# Monitait_V2.net
KiCad netlist of a schematic drawn in Altium Designer
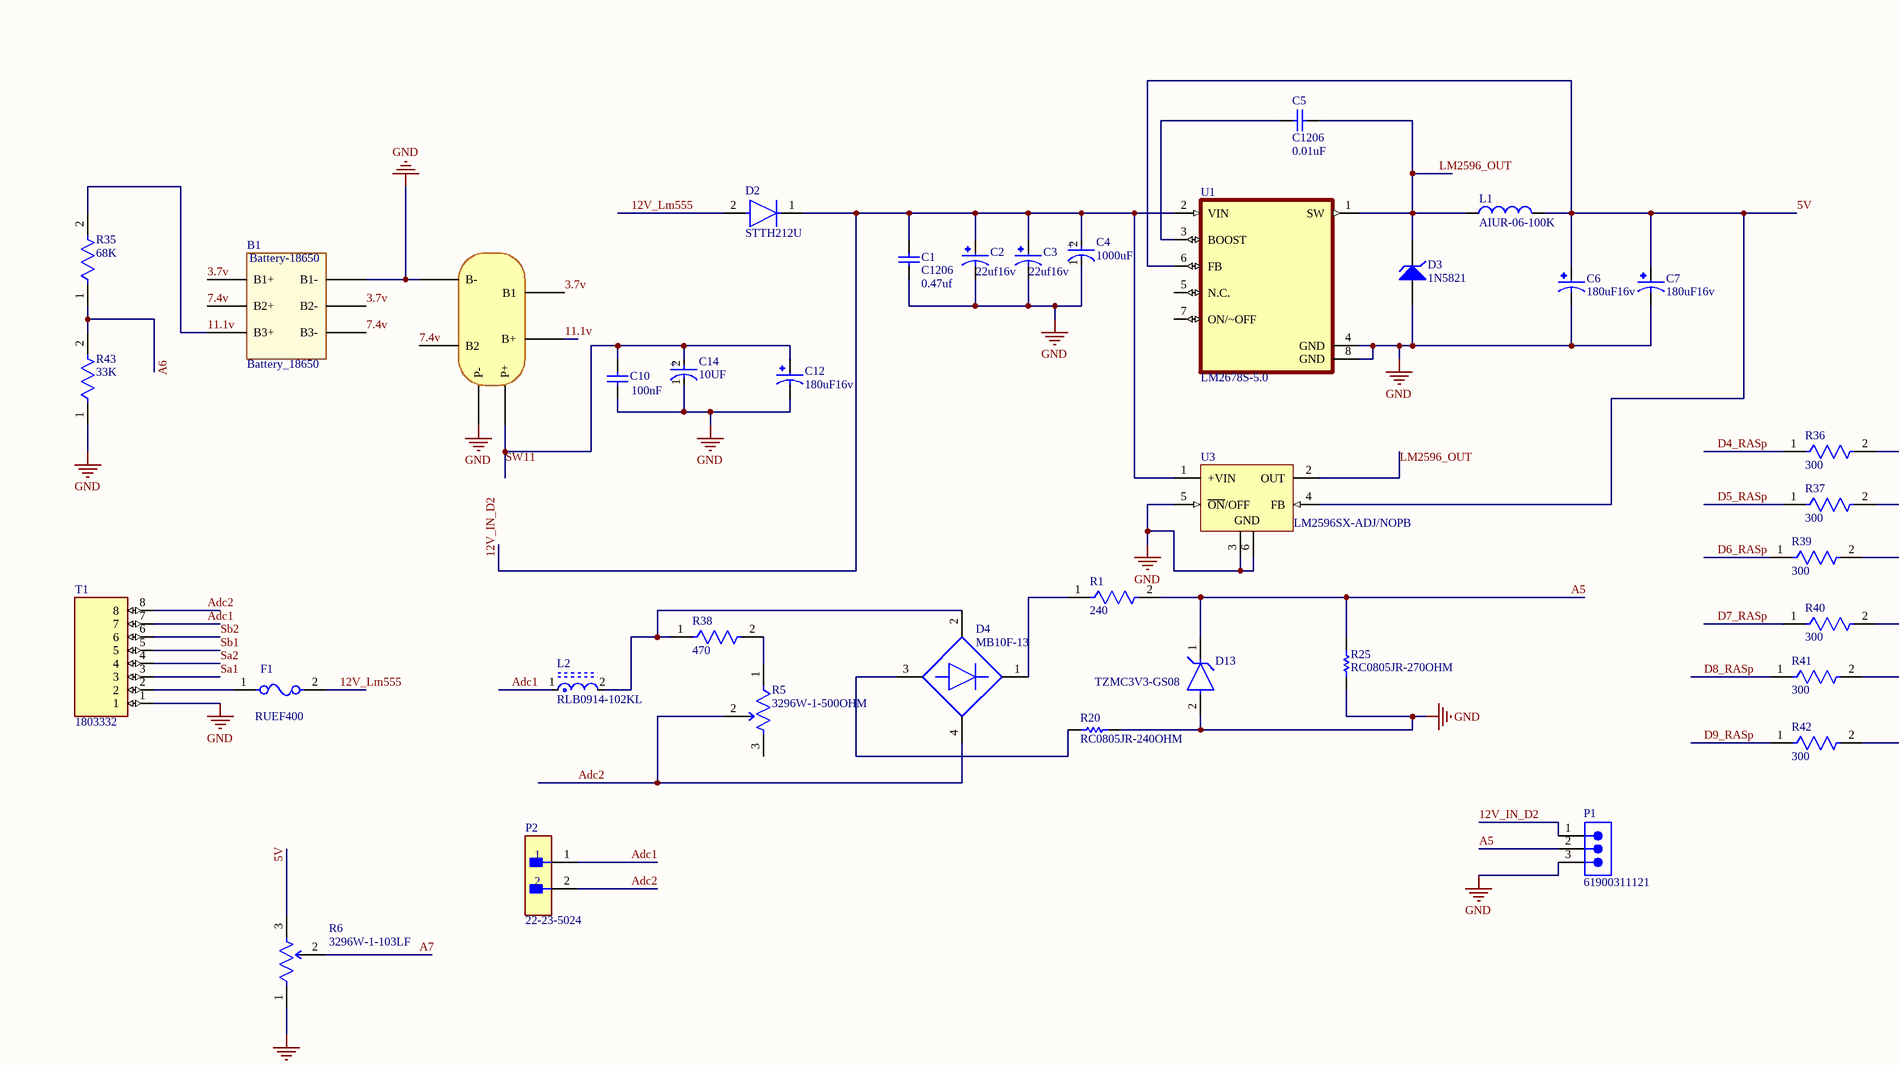
[diagram p0: Monitait_V2.SchDoc, top left]
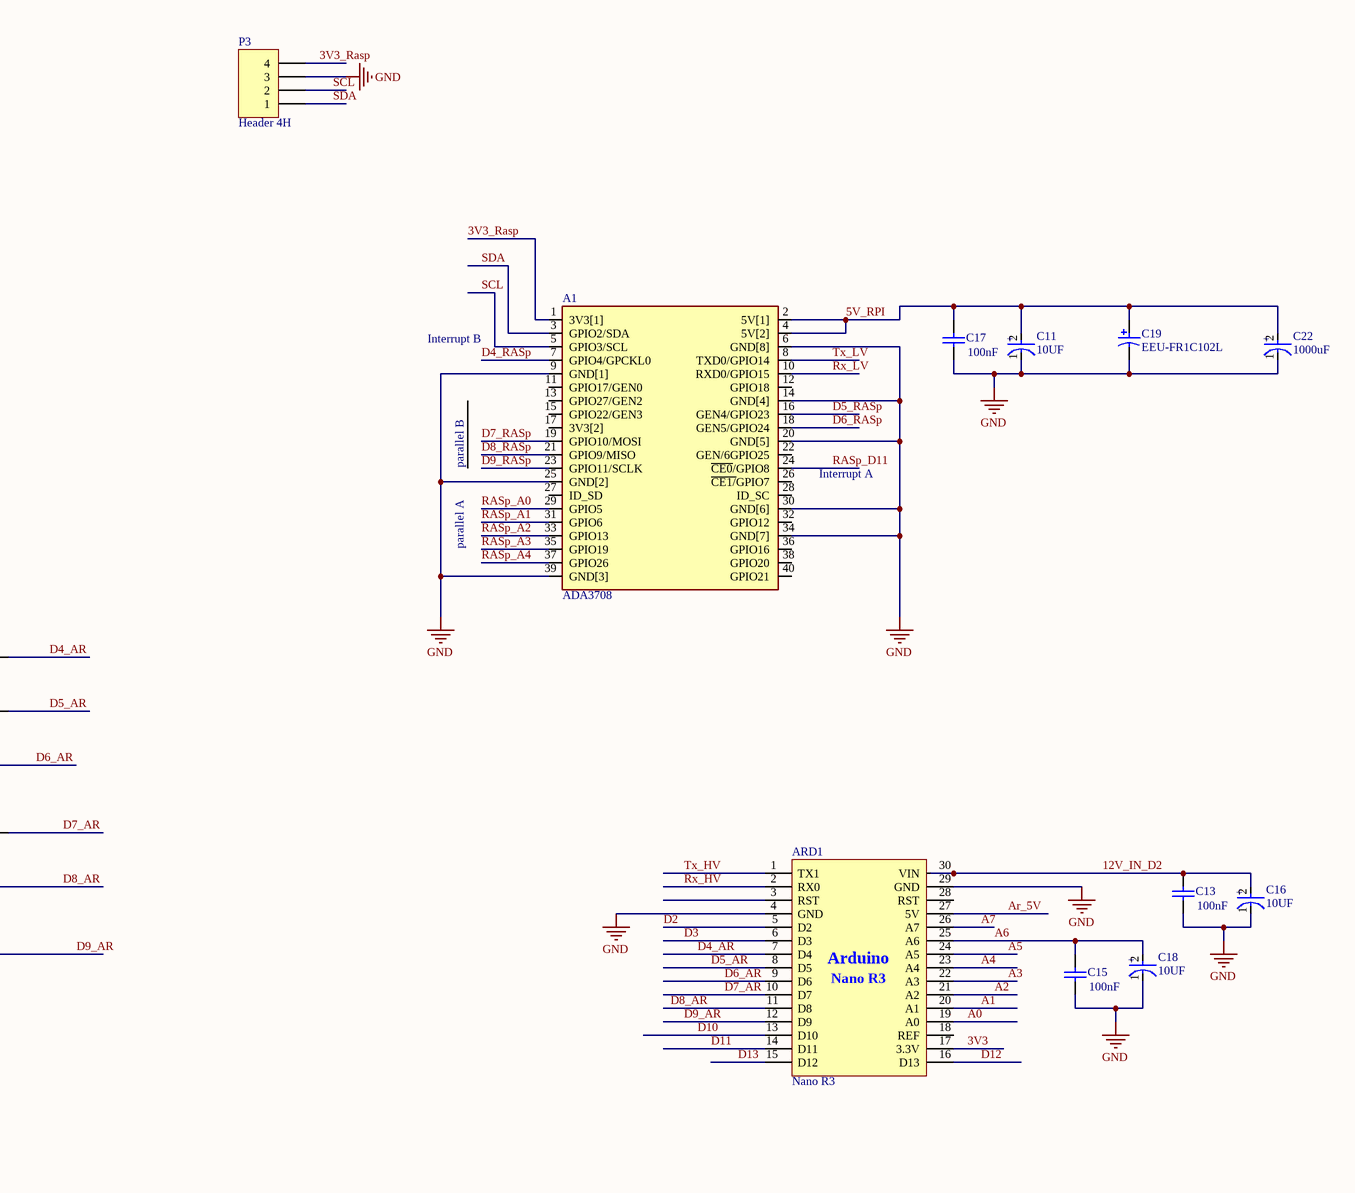
[diagram p1: Monitait_V2.SchDoc, top middle]
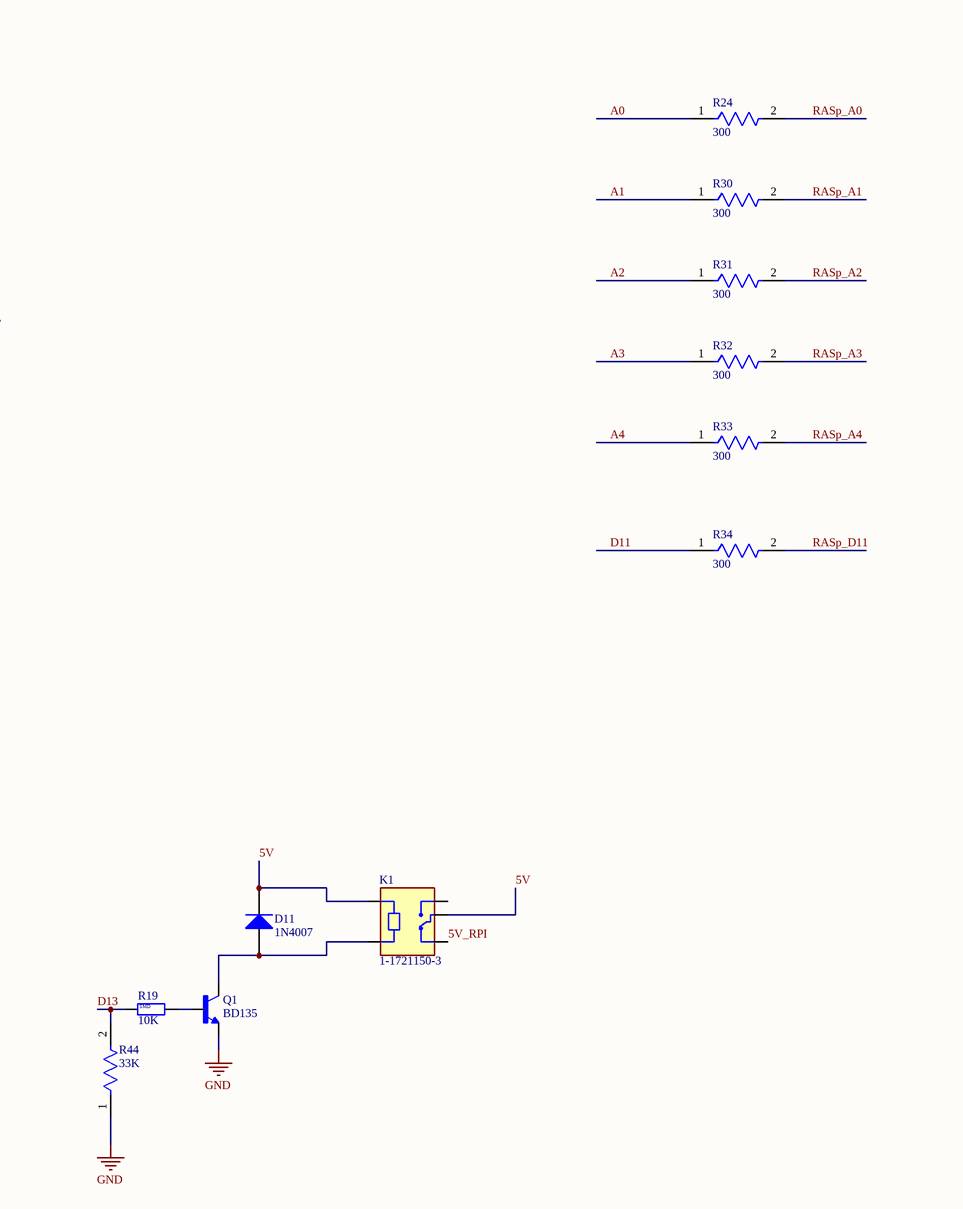
[diagram p2: Monitait_V2.SchDoc, top right]
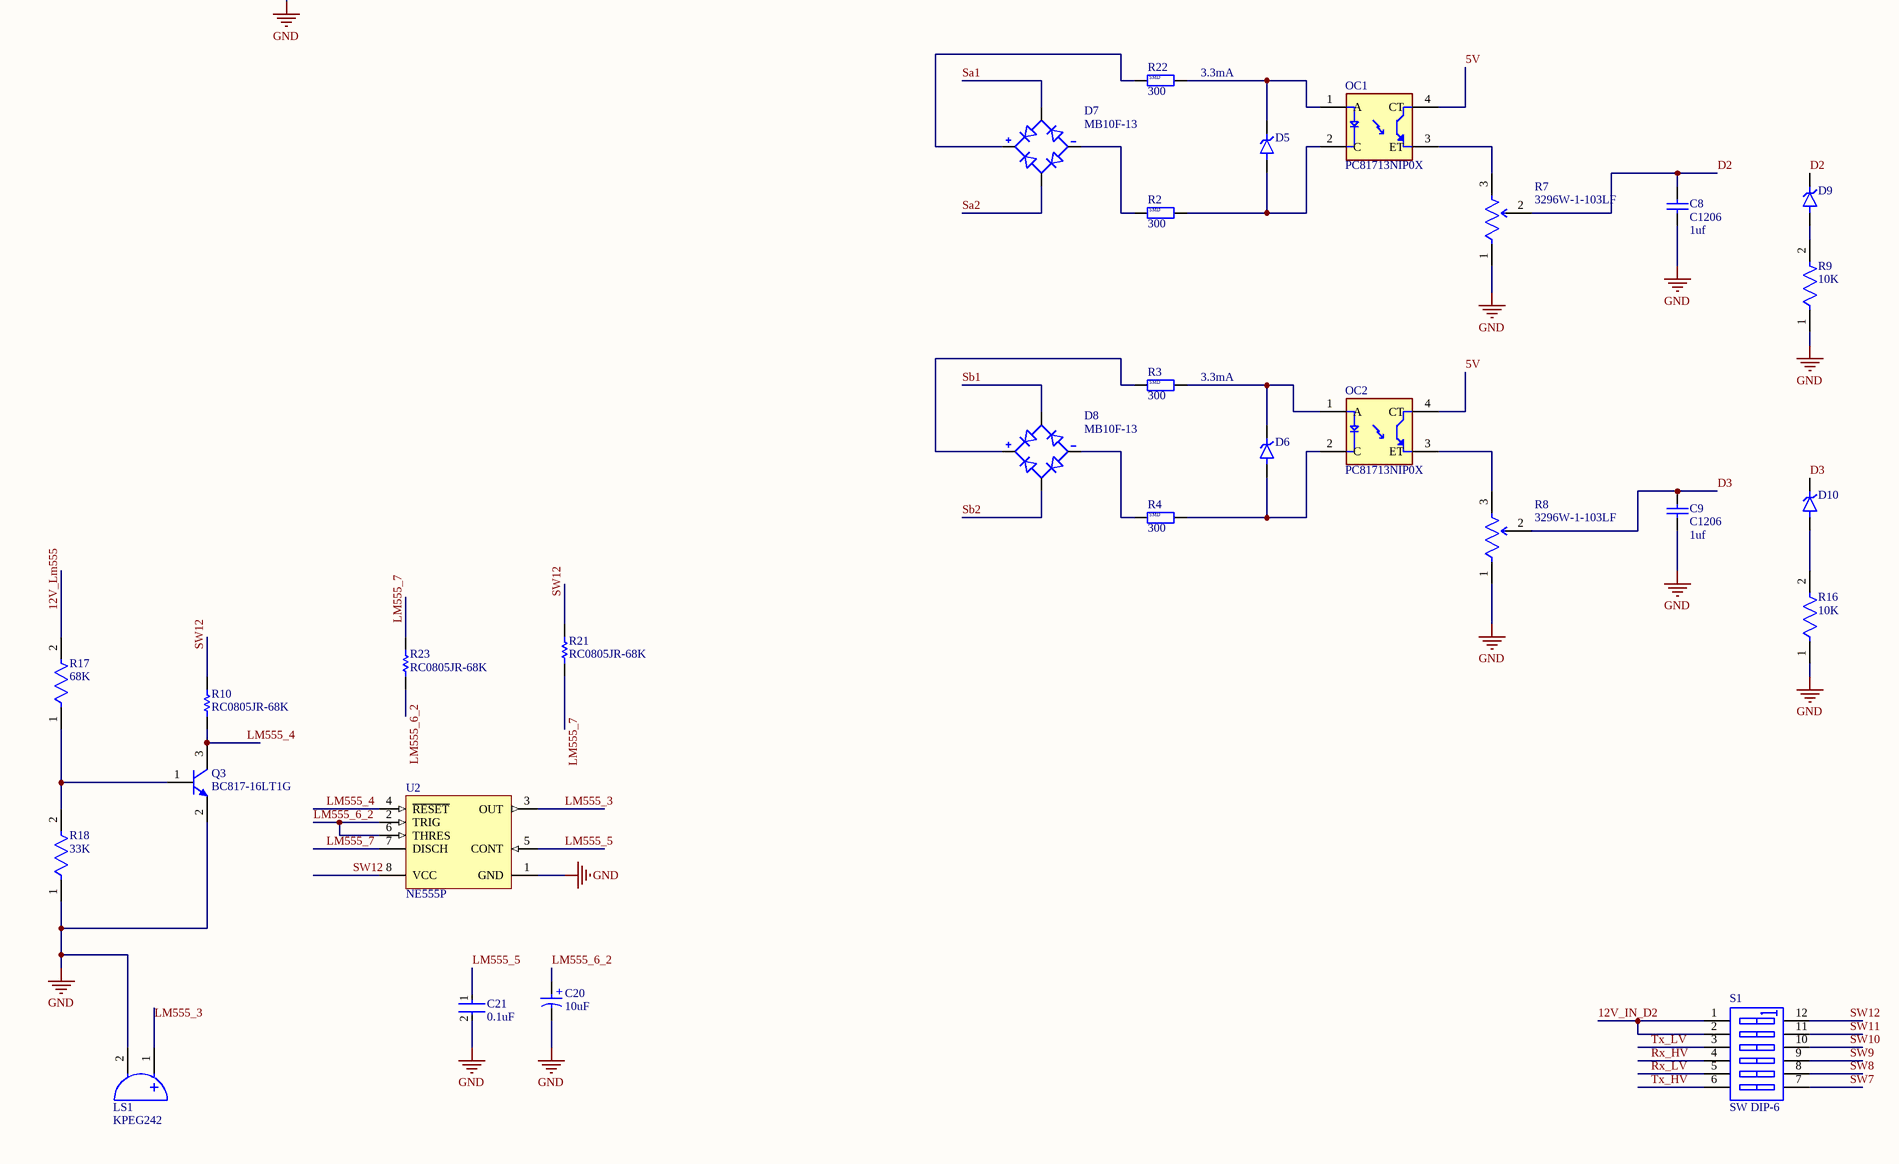
[diagram p3: Monitait_V2.SchDoc, bottom left]
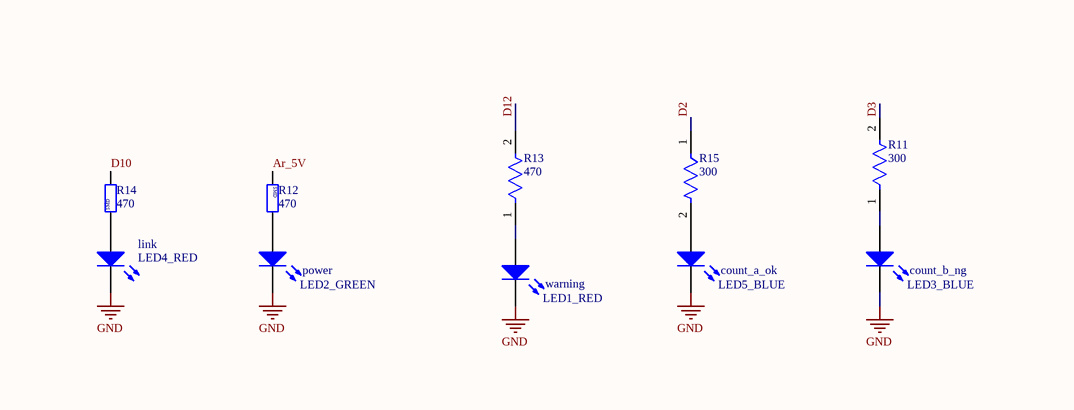
[diagram p4: Monitait_V2.SchDoc, bottom middle]
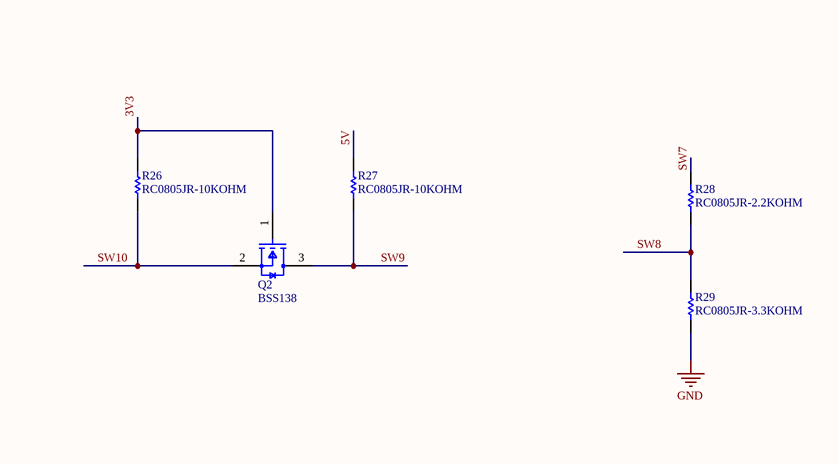
[diagram p5: Monitait_V2.SchDoc, bottom right]

(export (version "E")
  (design (tool "Eeschema 10.0.6"))
  (components
    (comp (ref "A1")
      (value "ADA3708")
      (footprint "ADA3708_RPI-ZERO")
      (description "Raspberry Pi Zero WH (Zero W with Headers)")
      (libsource (lib "ADA3708") (part "ADA3708"))
    )
    (comp (ref "ARD1")
      (value "Nano R3")
      (footprint "Arduino_Nano_R3")
      (description "Arduino Nano R3")
      (libsource (lib "Arduino") (part "Arduino Nano R3"))
    )
    (comp (ref "B1")
      (value "Battery_18650")
      (footprint "Battery-18650")
      (libsource (lib "Battery-18650") (part "Battery_18650"))
    )
    (comp (ref "C1")
      (value "C1206")
      (footprint "1206")
      (description "Ceramic Chip Capacitor - Standard")
      (fields (field (name "ALTIUM_VALUE") "0.47uf") (field (name "PUBLISHER") "Altium Limited"))
      (libsource (lib "KEMET Chip Capacitor") (part "C1206"))
    )
    (comp (ref "C2")
      (value "22uf16v")
      (footprint "CAPPRD500W45D500H500")
      (description "CAP ALUM 22UF 20% 16V RADIAL")
      (fields (field (name "MF") "Panasonic") (field (name "MP") "ECE-A1CKS220B"))
      (libsource (lib "c22uf16v") (part "ECEA1CKS220B"))
    )
    (comp (ref "C3")
      (value "22uf16v")
      (footprint "CAPPRD500W45D500H500")
      (description "CAP ALUM 22UF 20% 16V RADIAL")
      (fields (field (name "MF") "Panasonic") (field (name "MP") "ECE-A1CKS220B"))
      (libsource (lib "c22uf16v") (part "ECEA1CKS220B"))
    )
    (comp (ref "C4")
      (value "1000uF")
      (footprint "FP-RAD-TH-D_8_0_5-L_15_1-MFG")
      (description "Aluminum Electrolytic Capacitors (Radial Lead Type) 1000uF ±20% 10V")
      (fields (field (name "VOLTAGE") "10V") (field (name "TOLERANCE") "20%"))
      (libsource (lib "Altium Content Vault") (part "a00bbbee19879c290e62620ae7e47b1"))
    )
    (comp (ref "C5")
      (value "C1206")
      (footprint "1206")
      (description "Ceramic Chip Capacitor - Standard")
      (fields (field (name "ALTIUM_VALUE") "0.01uF") (field (name "PUBLISHER") "Altium Limited"))
      (libsource (lib "KEMET Chip Capacitor") (part "C1206"))
    )
    (comp (ref "C6")
      (value "180uF16v")
      (footprint "CAPPRD250W50D630H1650")
      (description "Cap Aluminum Lytic 180uF 16V 20% (6.3 X 15mm) Radial 2.5mm 285mA 2000h 105Â°C Ammo")
      (fields (field (name "MF") "Nichicon") (field (name "MP") "UPM1C181MED1TD"))
      (libsource (lib "c180uf16v_UPM1C181MED1TD") (part "UPM1C181MED1TD"))
    )
    (comp (ref "C7")
      (value "180uF16v")
      (footprint "CAPPRD250W50D630H1650")
      (description "Cap Aluminum Lytic 180uF 16V 20% (6.3 X 15mm) Radial 2.5mm 285mA 2000h 105Â°C Ammo")
      (fields (field (name "MF") "Nichicon") (field (name "MP") "UPM1C181MED1TD"))
      (libsource (lib "c180uf16v_UPM1C181MED1TD") (part "UPM1C181MED1TD"))
    )
    (comp (ref "C8")
      (value "C1206")
      (footprint "1206")
      (description "Ceramic Chip Capacitor - Standard")
      (fields (field (name "ALTIUM_VALUE") "1uf") (field (name "PUBLISHER") "Altium Limited"))
      (libsource (lib "KEMET Chip Capacitor") (part "C1206"))
    )
    (comp (ref "C9")
      (value "C1206")
      (footprint "1206")
      (description "Ceramic Chip Capacitor - Standard")
      (fields (field (name "ALTIUM_VALUE") "1uf") (field (name "PUBLISHER") "Altium Limited"))
      (libsource (lib "KEMET Chip Capacitor") (part "C1206"))
    )
    (comp (ref "C10")
      (value "100nF")
      (footprint "1206")
      (description "Ceramic Chip Capacitor - Standard")
      (fields (field (name "Comment") "C1206") (field (name "PUBLISHER") "Altium Limited"))
      (libsource (lib "KEMET Chip Capacitor") (part "C1206"))
    )
    (comp (ref "C11")
      (value "10UF")
      (footprint "FP-T491B106K020AT-MFG")
      (description "CAP TANT 10UF 10% 20V 1411")
      (fields (field (name "TOLERANCE") "10%") (field (name "VOLTAGE") "20V"))
      (libsource (lib "Altium Content Vault") (part "a00bbbee19879c290e62620ae7e47b1"))
    )
    (comp (ref "C12")
      (value "180uF16v")
      (footprint "CAPPRD250W50D630H1650")
      (description "Cap Aluminum Lytic 180uF 16V 20% (6.3 X 15mm) Radial 2.5mm 285mA 2000h 105Â°C Ammo")
      (fields (field (name "MF") "Nichicon") (field (name "MP") "UPM1C181MED1TD"))
      (libsource (lib "c180uf16v_UPM1C181MED1TD") (part "UPM1C181MED1TD"))
    )
    (comp (ref "C13")
      (value "100nF")
      (footprint "1206")
      (description "Ceramic Chip Capacitor - Standard")
      (fields (field (name "Comment") "C1206") (field (name "PUBLISHER") "Altium Limited"))
      (libsource (lib "KEMET Chip Capacitor") (part "C1206"))
    )
    (comp (ref "C14")
      (value "10UF")
      (footprint "FP-T491B106K020AT-MFG")
      (description "CAP TANT 10UF 10% 20V 1411")
      (fields (field (name "TOLERANCE") "10%") (field (name "VOLTAGE") "20V"))
      (libsource (lib "Altium Content Vault") (part "a00bbbee19879c290e62620ae7e47b1"))
    )
    (comp (ref "C15")
      (value "100nF")
      (footprint "1206")
      (description "Ceramic Chip Capacitor - Standard")
      (fields (field (name "Comment") "C1206") (field (name "PUBLISHER") "Altium Limited"))
      (libsource (lib "KEMET Chip Capacitor") (part "C1206"))
    )
    (comp (ref "C16")
      (value "10UF")
      (footprint "FP-T491B106K020AT-MFG")
      (description "CAP TANT 10UF 10% 20V 1411")
      (fields (field (name "TOLERANCE") "10%") (field (name "VOLTAGE") "20V"))
      (libsource (lib "Altium Content Vault") (part "a00bbbee19879c290e62620ae7e47b1"))
    )
    (comp (ref "C17")
      (value "100nF")
      (footprint "1206")
      (description "Ceramic Chip Capacitor - Standard")
      (fields (field (name "Comment") "C1206") (field (name "PUBLISHER") "Altium Limited"))
      (libsource (lib "KEMET Chip Capacitor") (part "C1206"))
    )
    (comp (ref "C18")
      (value "10UF")
      (footprint "FP-T491B106K020AT-MFG")
      (description "CAP TANT 10UF 10% 20V 1411")
      (fields (field (name "TOLERANCE") "10%") (field (name "VOLTAGE") "20V"))
      (libsource (lib "Altium Content Vault") (part "a00bbbee19879c290e62620ae7e47b1"))
    )
    (comp (ref "C19")
      (value "EEU-FR1C102L")
      (footprint "PNSC-FR-A-8X20-2_V")
      (fields (field (name "TOLERANCE") "+/- 20%") (field (name "MANUFACTURER") "Panasonic"))
      (libsource (lib "Altium Content Vault") (part "PNSC-CAP-P-2"))
    )
    (comp (ref "C20")
      (value "10uF")
      (footprint "WCAP-ATLL_D8H11.5")
      (description "860160574013 WCAP-ATLL Aluminum Electrolytic Capacitors")
      (fields (field (name "TOLERANCE") "20%"))
      (libsource (lib "Altium Content Vault") (part "Capacitor_Polarized"))
    )
    (comp (ref "C21")
      (value "0.1uF")
      (footprint "FP-K15H5-MFG")
      (description "CAP CER 0.1UF 50V X7R RADIAL")
      (fields (field (name "VOLTAGE") "50V") (field (name "TOLERANCE") "10%"))
      (libsource (lib "Altium Content Vault") (part "11868f565c42a9108669ba33697ecf6"))
    )
    (comp (ref "C22")
      (value "1000uF")
      (footprint "FP-RAD-TH-D_8_0_5-L_15_1-MFG")
      (description "Aluminum Electrolytic Capacitors (Radial Lead Type) 1000uF ±20% 10V")
      (fields (field (name "VOLTAGE") "10V") (field (name "TOLERANCE") "20%"))
      (libsource (lib "Altium Content Vault") (part "a00bbbee19879c290e62620ae7e47b1"))
    )
    (comp (ref "count_a_ok")
      (value "LED5_BLUE")
      (footprint "LED-3mm")
      (description "Typical LED")
      (fields (field (name "DESIGNER") "Seyed Mohsen Ghasemian") (field (name "PUBLISHER") "www.picpars.com"))
      (libsource (lib "usefully_Library") (part "LED 3mm"))
    )
    (comp (ref "count_b_ng")
      (value "LED3_BLUE")
      (footprint "LED-3mm")
      (description "Typical LED")
      (fields (field (name "DESIGNER") "Seyed Mohsen Ghasemian") (field (name "PUBLISHER") "www.picpars.com"))
      (libsource (lib "usefully_Library") (part "LED 3mm"))
    )
    (comp (ref "D2")
      (value "STTH212U")
      (footprint "FP-SMB-MFG")
      (description "DIODE GEN PURP 1.2KV 2A SMB")
      (fields
        (field (name "MANUFACTURER") "STMicroelectronics")
        (field (name "OCTOPART") "https://octopart.com/stth212u-stmicroelectronics-658227")
      )
      (libsource (lib "Altium Content Vault") (part "bbad89a4e1b75021f221062c6e04887"))
    )
    (comp (ref "D3")
      (value "1N5821")
      (footprint "299-02")
      (description "500 mW Hermetically Sealed Glass Silicon Zener Diode")
      (fields (field (name "PUBLISHER") "Altium Limited"))
      (libsource (lib "Motorola Discrete Diode") (part "1N746A"))
    )
    (comp (ref "D4")
      (value "MB10F-13")
      (footprint "FP-MBF-MFG")
      (description "BRIDGE RECT 1PHASE 1KV 800MA MBF")
      (fields
        (field (name "MANUFACTURER") "Diodes Incorporated")
        (field (name "OCTOPART") "https://octopart.com/mb10f-13-diodes+inc.-82160020")
      )
      (libsource (lib "Altium Content Vault") (part "c68dd78a3063a12c899a8333093fd1a"))
    )
    (comp (ref "D5")
      (value "LLZ5248B")
      (footprint "DIOMELF3515N")
      (description "Zener Diode Single 18V 5% 21Ohm 500mW 2-Pin Mini-MELF")
      (fields (field (name "MF") "Taiwan Semiconductor"))
      (libsource (lib "LLZ5248B") (part "LLZ5248B"))
    )
    (comp (ref "D6")
      (value "LLZ5248B")
      (footprint "DIOMELF3515N")
      (description "Zener Diode Single 18V 5% 21Ohm 500mW 2-Pin Mini-MELF")
      (fields (field (name "MF") "Taiwan Semiconductor"))
      (libsource (lib "LLZ5248B") (part "LLZ5248B"))
    )
    (comp (ref "D7")
      (value "MB10F-13")
      (footprint "DIOB_MB10F-13")
      (description "Bridge Rectifier Single Phase Standard 1 kV Surface Mount MBF")
      (fields (field (name "MF") "Diodes Inc."))
      (libsource (lib "MB10F-13") (part "MB10F-13"))
    )
    (comp (ref "D8")
      (value "MB10F-13")
      (footprint "DIOB_MB10F-13")
      (description "Bridge Rectifier Single Phase Standard 1 kV Surface Mount MBF")
      (fields (field (name "MF") "Diodes Inc."))
      (libsource (lib "MB10F-13") (part "MB10F-13"))
    )
    (comp (ref "D9")
      (value "LLZ5248B")
      (footprint "DIOMELF3515N")
      (description "Zener Diode Single 18V 5% 21Ohm 500mW 2-Pin Mini-MELF")
      (fields (field (name "MF") "Taiwan Semiconductor"))
      (libsource (lib "LLZ5248B") (part "LLZ5248B"))
    )
    (comp (ref "D10")
      (value "LLZ5248B")
      (footprint "DIOMELF3515N")
      (description "Zener Diode Single 18V 5% 21Ohm 500mW 2-Pin Mini-MELF")
      (fields (field (name "MF") "Taiwan Semiconductor"))
      (libsource (lib "LLZ5248B") (part "LLZ5248B"))
    )
    (comp (ref "D11")
      (value "1N4007")
      (footprint "My_DO-41")
      (description "1 Amp Diode")
      (libsource (lib "Altium library (www.AVRelec.com)") (part "1N4007"))
    )
    (comp (ref "D13")
      (value "TZMC3V3-GS08")
      (footprint "FP-6_560-5005_01-4-MFG")
      (description "DIODE ZENER 3.3V 500MW SOD80")
      (fields
        (field (name "MANUFACTURER") "Vishay")
        (field (name "OCTOPART") "https://octopart.com/tzmc3v3-gs08-vishay-55388698")
      )
      (libsource (lib "Altium Content Vault") (part "f813f71cba58e380607f5dd3caf9714"))
    )
    (comp (ref "F1")
      (value "RUEF400")
      (footprint "FP-RUEF400-MFG")
      (description "PTC RESET FUSE 30V 4A RADIAL")
      (fields
        (field (name "MANUFACTURER") "Littelfuse")
        (field (name "OCTOPART") "https://octopart.com/ruef400-littelfuse-74215791")
      )
      (libsource (lib "Altium Content Vault") (part "5bcf9b9f640e542cf0359d10258e979"))
    )
    (comp (ref "K1")
      (value "1-1721150-3")
      (footprint "RELAY_1-1721150-3")
      (libsource (lib "1-1721150-3") (part "1-1721150-3"))
    )
    (comp (ref "L1")
      (value "AIUR-06-100K")
      (footprint "ABRA-AIUR-06-2_V")
      (description "Fixed Inductor, 10 uH, +/- 10%, -40 to 85 degC, 2-Pin THD, RoHS, Bulk")
      (fields (field (name "MANUFACTURER") "ABRACON") (field (name "TOLERANCE") "10%"))
      (libsource (lib "Altium Content Vault") (part "IND-2"))
    )
    (comp (ref "L2")
      (value "RLB0914-102KL")
      (footprint "FP-RLB0914-MFG")
      (description "FIXED IND 1MH 420MA 2.1 OHM TH")
      (fields (field (name "TOLERANCE") "10%"))
      (libsource (lib "Altium Content Vault") (part "6087e8490c250d489263be6a42f1ae3"))
    )
    (comp (ref "link")
      (value "LED4_RED")
      (footprint "LED-3mm")
      (description "Typical LED")
      (fields (field (name "DESIGNER") "Seyed Mohsen Ghasemian") (field (name "PUBLISHER") "www.picpars.com"))
      (libsource (lib "usefully_Library") (part "LED 3mm"))
    )
    (comp (ref "LS1")
      (value "KPEG242")
      (footprint "KINGS-KPEG242-2")
      (description "Piezo Indicator, 4100 Hz, 3 to 16 V, -20 to 70 degC, 2-Pin THD, RoHS")
      (fields (field (name "PARTNUMBER") "KPE-242") (field (name "MANUFACTURER") "KingstateElectronicsCorp."))
      (libsource (lib "Altium Content Vault") (part "KINGS-KPEG242-2"))
    )
    (comp (ref "M1") (value "FL10A") (footprint "FL10A") (libsource (lib "FL10A") (part "FL10A")))
    (comp (ref "OC1")
      (value "PC81713NIP0X")
      (footprint "SOT254P1025X400-4N")
      (description "Optoisolator Transistor Output 5000Vrms 1 Channel 4-SMD")
      (fields (field (name "MF") "SHARP/Socle Technology"))
      (libsource (lib "PC81713NIP0X") (part "PC81713NIP0X"))
    )
    (comp (ref "OC2")
      (value "PC81713NIP0X")
      (footprint "SOT254P1025X400-4N")
      (description "Optoisolator Transistor Output 5000Vrms 1 Channel 4-SMD")
      (fields (field (name "MF") "SHARP/Socle Technology"))
      (libsource (lib "PC81713NIP0X") (part "PC81713NIP0X"))
    )
    (comp (ref "P1")
      (value "61900311121")
      (footprint "61900311121")
      (libsource (lib "Altium Content Vault") (part "Header_Male_1R_03P"))
    )
    (comp (ref "P2")
      (value "22-23-5024")
      (footprint "FP-22-23-5024-MFG")
      (description "CONN HEADER VERT 2POS 2.54MM")
      (fields
        (field (name "MANUFACTURER") "Molex")
        (field (name "OCTOPART") "https://octopart.com/22-23-5024-molex-6792956")
      )
      (libsource (lib "Altium Content Vault") (part "3bc925449376181038e59eaffc5286c"))
    )
    (comp (ref "P3")
      (value "Header 4H")
      (footprint "HDR1X4H")
      (description "Header, 4-Pin, Right Angle")
      (fields (field (name "PUBLISHER") "Altium Limited"))
      (libsource (lib "Miscellaneous Connectors") (part "Header 4H"))
    )
    (comp (ref "power")
      (value "LED2_GREEN")
      (footprint "LED-3mm")
      (description "Typical LED")
      (fields (field (name "DESIGNER") "Seyed Mohsen Ghasemian") (field (name "PUBLISHER") "www.picpars.com"))
      (libsource (lib "usefully_Library") (part "LED 3mm"))
    )
    (comp (ref "Q1")
      (value "BD135")
      (footprint "TO229P780X300X2000-3")
      (fields (field (name "MF") "ON Semiconductor"))
      (libsource (lib "BD135") (part "BD135"))
    )
    (comp (ref "Q2")
      (value "BSS138")
      (footprint "FP-318-08-IPC_B")
      (description "MOSFET N-CH 50V 220MA SOT-23")
      (libsource (lib "Altium Content Vault") (part "3b9c635fedb024a5347a57b145af9cc"))
    )
    (comp (ref "Q3")
      (value "BC817-16LT1G")
      (footprint "ONSC-SOT-23-3-318-08_V")
      (description "General Purpose Transistor, NPN Silicon, 3-Pin SOT-23, Pb-Free, Tape and Reel")
      (fields (field (name "MANUFACTURER") "On Semiconductor"))
      (libsource (lib "Altium Content Vault") (part "ONSC-NPN-B1E2C3-3"))
    )
    (comp (ref "R1")
      (value "240")
      (footprint "FP-CRCW1206-e3-IPC_C")
      (description "RES Thick Film, 118kΩ, 1%, 0.25W, 100ppm/°C, 1206")
      (fields (field (name "TOLERANCE") "1%"))
      (libsource (lib "Altium Content Vault") (part "1029c3af85768c4190bb7ad29bc67b5"))
    )
    (comp (ref "R2")
      (value "300")
      (footprint "1206")
      (description "Resistor")
      (fields (field (name "PUBLISHER") "Altium Limited"))
      (libsource (lib "AK-Resistor") (part "Resistor SMD"))
    )
    (comp (ref "R3")
      (value "300")
      (footprint "1206")
      (description "Resistor")
      (fields (field (name "PUBLISHER") "Altium Limited"))
      (libsource (lib "AK-Resistor") (part "Resistor SMD"))
    )
    (comp (ref "R4")
      (value "300")
      (footprint "1206")
      (description "Resistor")
      (fields (field (name "PUBLISHER") "Altium Limited"))
      (libsource (lib "AK-Resistor") (part "Resistor SMD"))
    )
    (comp (ref "R5")
      (value "3296W-1-500OHM")
      (footprint "FP-3296W-MFG")
      (description "TRIMMER 10K OHM 0.5W PC PIN TOP")
      (fields (field (name "TOLERANCE") "10%"))
      (libsource (lib "Altium Content Vault") (part "2dcfd2547301a7d3209a5e99acfd772"))
    )
    (comp (ref "R6")
      (value "3296W-1-103LF")
      (footprint "FP-3296W-MFG")
      (description "TRIMMER 10K OHM 0.5W PC PIN TOP")
      (fields (field (name "TOLERANCE") "10%"))
      (libsource (lib "Altium Content Vault") (part "2dcfd2547301a7d3209a5e99acfd772"))
    )
    (comp (ref "R7")
      (value "3296W-1-103LF")
      (footprint "FP-3296W-MFG")
      (description "TRIMMER 10K OHM 0.5W PC PIN TOP")
      (fields (field (name "TOLERANCE") "10%"))
      (libsource (lib "Altium Content Vault") (part "2dcfd2547301a7d3209a5e99acfd772"))
    )
    (comp (ref "R8")
      (value "3296W-1-103LF")
      (footprint "FP-3296W-MFG")
      (description "TRIMMER 10K OHM 0.5W PC PIN TOP")
      (fields (field (name "TOLERANCE") "10%"))
      (libsource (lib "Altium Content Vault") (part "2dcfd2547301a7d3209a5e99acfd772"))
    )
    (comp (ref "R9")
      (value "10K")
      (footprint "FP-CRCW1206-e3-IPC_C")
      (description "RES Thick Film, 118kΩ, 1%, 0.25W, 100ppm/°C, 1206")
      (fields (field (name "TOLERANCE") "1%"))
      (libsource (lib "Altium Content Vault") (part "1029c3af85768c4190bb7ad29bc67b5"))
    )
    (comp (ref "R10")
      (value "RC0805JR-68K")
      (footprint "RESC2013X60X35ML10T20")
      (fields (field (name "TOLERANCE") "5%") (field (name "MANUFACTURER") "Yageo"))
      (libsource (lib "Altium Content Vault") (part "RES-2"))
    )
    (comp (ref "R11")
      (value "300")
      (footprint "FP-CRCW1206-e3-IPC_C")
      (description "RES Thick Film, 118kΩ, 1%, 0.25W, 100ppm/°C, 1206")
      (fields (field (name "TOLERANCE") "1%"))
      (libsource (lib "Altium Content Vault") (part "1029c3af85768c4190bb7ad29bc67b5"))
    )
    (comp (ref "R12")
      (value "470")
      (footprint "1206")
      (description "Resistor")
      (fields (field (name "PUBLISHER") "Altium Limited"))
      (libsource (lib "") (part "Resistor SMD_2"))
    )
    (comp (ref "R13")
      (value "470")
      (footprint "FP-CRCW1206-e3-IPC_C")
      (description "RES Thick Film, 118kΩ, 1%, 0.25W, 100ppm/°C, 1206")
      (fields (field (name "TOLERANCE") "1%"))
      (libsource (lib "Altium Content Vault") (part "1029c3af85768c4190bb7ad29bc67b5"))
    )
    (comp (ref "R14")
      (value "470")
      (footprint "1206")
      (description "Resistor")
      (fields (field (name "PUBLISHER") "Altium Limited"))
      (libsource (lib "") (part "Resistor SMD_1"))
    )
    (comp (ref "R15")
      (value "300")
      (footprint "FP-CRCW1206-e3-IPC_C")
      (description "RES Thick Film, 118kΩ, 1%, 0.25W, 100ppm/°C, 1206")
      (fields (field (name "TOLERANCE") "1%"))
      (libsource (lib "Altium Content Vault") (part "1029c3af85768c4190bb7ad29bc67b5"))
    )
    (comp (ref "R16")
      (value "10K")
      (footprint "FP-CRCW1206-e3-IPC_C")
      (description "RES Thick Film, 118kΩ, 1%, 0.25W, 100ppm/°C, 1206")
      (fields (field (name "TOLERANCE") "1%"))
      (libsource (lib "Altium Content Vault") (part "1029c3af85768c4190bb7ad29bc67b5"))
    )
    (comp (ref "R17")
      (value "68K")
      (footprint "FP-CRCW1206-e3-IPC_C")
      (description "RES Thick Film, 118kΩ, 1%, 0.25W, 100ppm/°C, 1206")
      (fields (field (name "TOLERANCE") "1%"))
      (libsource (lib "Altium Content Vault") (part "1029c3af85768c4190bb7ad29bc67b5"))
    )
    (comp (ref "R18")
      (value "33K")
      (footprint "FP-CRCW1206-e3-IPC_C")
      (description "RES Thick Film, 118kΩ, 1%, 0.25W, 100ppm/°C, 1206")
      (fields (field (name "TOLERANCE") "1%"))
      (libsource (lib "Altium Content Vault") (part "1029c3af85768c4190bb7ad29bc67b5"))
    )
    (comp (ref "R19")
      (value "10K")
      (footprint "1206")
      (description "Resistor")
      (fields (field (name "PUBLISHER") "Altium Limited"))
      (libsource (lib "AK-Resistor") (part "Resistor SMD"))
    )
    (comp (ref "R20")
      (value "RC0805JR-240OHM")
      (footprint "RESC2013X60X35ML10T20")
      (fields (field (name "TOLERANCE") "5%") (field (name "MANUFACTURER") "Yageo"))
      (libsource (lib "Altium Content Vault") (part "RES-2"))
    )
    (comp (ref "R21")
      (value "RC0805JR-68K")
      (footprint "RESC2013X60X35ML10T20")
      (fields (field (name "TOLERANCE") "5%") (field (name "MANUFACTURER") "Yageo"))
      (libsource (lib "Altium Content Vault") (part "RES-2"))
    )
    (comp (ref "R22")
      (value "300")
      (footprint "1206")
      (description "Resistor")
      (fields (field (name "PUBLISHER") "Altium Limited"))
      (libsource (lib "AK-Resistor") (part "Resistor SMD"))
    )
    (comp (ref "R23")
      (value "RC0805JR-68K")
      (footprint "RESC2013X60X35ML10T20")
      (fields (field (name "TOLERANCE") "5%") (field (name "MANUFACTURER") "Yageo"))
      (libsource (lib "Altium Content Vault") (part "RES-2"))
    )
    (comp (ref "R24")
      (value "300")
      (footprint "FP-CRCW1206-e3-IPC_B")
      (description "RES Thick Film, 100Ω, 1%, 0.25W, 100ppm/°C, 1206")
      (fields (field (name "TOLERANCE") "1%"))
      (libsource (lib "Altium Content Vault") (part "1029c3af85768c4190bb7ad29bc67b5"))
    )
    (comp (ref "R25")
      (value "RC0805JR-270OHM")
      (footprint "RESC2013X60X35ML10T20")
      (fields (field (name "TOLERANCE") "5%") (field (name "MANUFACTURER") "Yageo"))
      (libsource (lib "Altium Content Vault") (part "RES-2"))
    )
    (comp (ref "R26")
      (value "RC0805JR-10KOHM")
      (footprint "RESC2013X60X35ML10T20")
      (fields (field (name "TOLERANCE") "5%") (field (name "MANUFACTURER") "Yageo"))
      (libsource (lib "Altium Content Vault") (part "RES-2"))
    )
    (comp (ref "R27")
      (value "RC0805JR-10KOHM")
      (footprint "RESC2013X60X35ML10T20")
      (fields (field (name "TOLERANCE") "5%") (field (name "MANUFACTURER") "Yageo"))
      (libsource (lib "Altium Content Vault") (part "RES-2"))
    )
    (comp (ref "R28")
      (value "RC0805JR-2.2KOHM")
      (footprint "RESC2013X60X35ML10T20")
      (fields (field (name "TOLERANCE") "5%") (field (name "MANUFACTURER") "Yageo"))
      (libsource (lib "Altium Content Vault") (part "RES-2"))
    )
    (comp (ref "R29")
      (value "RC0805JR-3.3KOHM")
      (footprint "RESC2013X60X35ML10T20")
      (fields (field (name "TOLERANCE") "5%") (field (name "MANUFACTURER") "Yageo"))
      (libsource (lib "Altium Content Vault") (part "RES-2"))
    )
    (comp (ref "R30")
      (value "300")
      (footprint "FP-CRCW1206-e3-IPC_B")
      (description "RES Thick Film, 100Ω, 1%, 0.25W, 100ppm/°C, 1206")
      (fields (field (name "TOLERANCE") "1%"))
      (libsource (lib "Altium Content Vault") (part "1029c3af85768c4190bb7ad29bc67b5"))
    )
    (comp (ref "R31")
      (value "300")
      (footprint "FP-CRCW1206-e3-IPC_B")
      (description "RES Thick Film, 100Ω, 1%, 0.25W, 100ppm/°C, 1206")
      (fields (field (name "TOLERANCE") "1%"))
      (libsource (lib "Altium Content Vault") (part "1029c3af85768c4190bb7ad29bc67b5"))
    )
    (comp (ref "R32")
      (value "300")
      (footprint "FP-CRCW1206-e3-IPC_B")
      (description "RES Thick Film, 100Ω, 1%, 0.25W, 100ppm/°C, 1206")
      (fields (field (name "TOLERANCE") "1%"))
      (libsource (lib "Altium Content Vault") (part "1029c3af85768c4190bb7ad29bc67b5"))
    )
    (comp (ref "R33")
      (value "300")
      (footprint "FP-CRCW1206-e3-IPC_B")
      (description "RES Thick Film, 100Ω, 1%, 0.25W, 100ppm/°C, 1206")
      (fields (field (name "TOLERANCE") "1%"))
      (libsource (lib "Altium Content Vault") (part "1029c3af85768c4190bb7ad29bc67b5"))
    )
    (comp (ref "R34")
      (value "300")
      (footprint "FP-CRCW1206-e3-IPC_B")
      (description "RES Thick Film, 100Ω, 1%, 0.25W, 100ppm/°C, 1206")
      (fields (field (name "TOLERANCE") "1%"))
      (libsource (lib "Altium Content Vault") (part "1029c3af85768c4190bb7ad29bc67b5"))
    )
    (comp (ref "R35")
      (value "68K")
      (footprint "FP-CRCW1206-e3-IPC_C")
      (description "RES Thick Film, 118kΩ, 1%, 0.25W, 100ppm/°C, 1206")
      (fields (field (name "TOLERANCE") "1%"))
      (libsource (lib "Altium Content Vault") (part "1029c3af85768c4190bb7ad29bc67b5"))
    )
    (comp (ref "R36")
      (value "300")
      (footprint "FP-CRCW1206-e3-IPC_C")
      (description "RES Thick Film, 118kΩ, 1%, 0.25W, 100ppm/°C, 1206")
      (fields (field (name "TOLERANCE") "1%"))
      (libsource (lib "Altium Content Vault") (part "1029c3af85768c4190bb7ad29bc67b5"))
    )
    (comp (ref "R37")
      (value "300")
      (footprint "FP-CRCW1206-e3-IPC_C")
      (description "RES Thick Film, 118kΩ, 1%, 0.25W, 100ppm/°C, 1206")
      (fields (field (name "TOLERANCE") "1%"))
      (libsource (lib "Altium Content Vault") (part "1029c3af85768c4190bb7ad29bc67b5"))
    )
    (comp (ref "R38")
      (value "470")
      (footprint "FP-CRCW1206-e3-IPC_C")
      (description "RES Thick Film, 118kΩ, 1%, 0.25W, 100ppm/°C, 1206")
      (fields (field (name "TOLERANCE") "1%"))
      (libsource (lib "Altium Content Vault") (part "1029c3af85768c4190bb7ad29bc67b5"))
    )
    (comp (ref "R39")
      (value "300")
      (footprint "FP-CRCW1206-e3-IPC_C")
      (description "RES Thick Film, 118kΩ, 1%, 0.25W, 100ppm/°C, 1206")
      (fields (field (name "TOLERANCE") "1%"))
      (libsource (lib "Altium Content Vault") (part "1029c3af85768c4190bb7ad29bc67b5"))
    )
    (comp (ref "R40")
      (value "300")
      (footprint "FP-CRCW1206-e3-IPC_C")
      (description "RES Thick Film, 118kΩ, 1%, 0.25W, 100ppm/°C, 1206")
      (fields (field (name "TOLERANCE") "1%"))
      (libsource (lib "Altium Content Vault") (part "1029c3af85768c4190bb7ad29bc67b5"))
    )
    (comp (ref "R41")
      (value "300")
      (footprint "FP-CRCW1206-e3-IPC_C")
      (description "RES Thick Film, 118kΩ, 1%, 0.25W, 100ppm/°C, 1206")
      (fields (field (name "TOLERANCE") "1%"))
      (libsource (lib "Altium Content Vault") (part "1029c3af85768c4190bb7ad29bc67b5"))
    )
    (comp (ref "R42")
      (value "300")
      (footprint "FP-CRCW1206-e3-IPC_C")
      (description "RES Thick Film, 118kΩ, 1%, 0.25W, 100ppm/°C, 1206")
      (fields (field (name "TOLERANCE") "1%"))
      (libsource (lib "Altium Content Vault") (part "1029c3af85768c4190bb7ad29bc67b5"))
    )
    (comp (ref "R43")
      (value "33K")
      (footprint "FP-CRCW1206-e3-IPC_C")
      (description "RES Thick Film, 118kΩ, 1%, 0.25W, 100ppm/°C, 1206")
      (fields (field (name "TOLERANCE") "1%"))
      (libsource (lib "Altium Content Vault") (part "1029c3af85768c4190bb7ad29bc67b5"))
    )
    (comp (ref "R44")
      (value "33K")
      (footprint "FP-CRCW1206-e3-IPC_C")
      (description "RES Thick Film, 118kΩ, 1%, 0.25W, 100ppm/°C, 1206")
      (fields (field (name "TOLERANCE") "1%"))
      (libsource (lib "Altium Content Vault") (part "1029c3af85768c4190bb7ad29bc67b5"))
    )
    (comp (ref "S1")
      (value "SW DIP-6")
      (footprint "DIP-12/SW")
      (description "DIP Switch, 6 Position, SPST")
      (fields (field (name "PUBLISHER") "Altium Limited"))
      (libsource (lib "Miscellaneous Devices") (part "SW DIP-6"))
    )
    (comp (ref "T1")
      (value "1803332")
      (footprint "SHDRRA8W83P0X381_1X8_3187X920X")
      (fields (field (name "MF") "Phoenix Contact"))
      (libsource (lib "phoenix8pin3.81mm_1803332") (part "1803332"))
    )
    (comp (ref "U1")
      (value "LM2678S-5.0")
      (footprint "TO127P1435X464-8N")
      (description "8V to 40V, 5A SIMPLE SWITCHER buck converter with high efficiency 7-DDPAK/TO-263 -40 to 125")
      (fields (field (name "MF") "Texas Instruments"))
      (libsource (lib "LM2678S-5.0") (part "LM2678S-5.0"))
    )
    (comp (ref "U2")
      (value "NE555P")
      (footprint "P0008A")
      (description "Precision Timer, 4.5 to 16 V, 0 to 70 degC, 8-Pin DIP, Pb-Free, Tube")
      (fields (field (name "MANUFACTURER") "TexasInstruments"))
      (libsource (lib "Altium Content Vault") (part "TI-NE555-P8"))
    )
    (comp (ref "U3")
      (value "LM2596SX-ADJ/NOPB")
      (footprint "KTT0005B_L")
      (fields (field (name "PARTNUMBER") "LM2596") (field (name "MANUFACTURER") "Texas Instruments"))
      (libsource (lib "Altium Content Vault") (part "TI-LM2596-TO-263-5"))
    )
    (comp (ref "warning")
      (value "LED1_RED")
      (footprint "LED-3mm")
      (description "Typical LED")
      (fields (field (name "DESIGNER") "Seyed Mohsen Ghasemian") (field (name "PUBLISHER") "www.picpars.com"))
      (libsource (lib "usefully_Library") (part "LED 3mm"))
    )
  )
  (nets
    (net (code "1") (name "/3.7v") (class "Default")
      (node (ref "B1") (pin "B1+") (pinfunction "B1+_B1+") (pintype "passive"))
      (node (ref "B1") (pin "B2-") (pinfunction "B2-_B2-") (pintype "passive"))
      (node (ref "M1") (pin "B1") (pinfunction "B1_B1") (pintype "passive"))
    )
    (net (code "2") (name "/3V3") (class "Default")
      (node (ref "ARD1") (pin "17") (pinfunction "3.3V_17") (pintype "power_in"))
      (node (ref "Q2") (pin "1") (pinfunction "G_1") (pintype "passive"))
      (node (ref "R26") (pin "2") (pinfunction "2_2") (pintype "passive"))
    )
    (net (code "3") (name "/3V3_Rasp") (class "Default")
      (node (ref "A1") (pin "1") (pinfunction "3V3[1]_1") (pintype "power_in"))
      (node (ref "P3") (pin "4") (pinfunction "4_4") (pintype "passive"))
    )
    (net (code "4") (name "/5V") (class "Default")
      (node (ref "C6") (pin "P") (pinfunction "P_P") (pintype "passive"))
      (node (ref "C7") (pin "P") (pinfunction "P_P") (pintype "passive"))
      (node (ref "D11") (pin "K") (pinfunction "K_K") (pintype "passive"))
      (node (ref "K1") (pin "A1") (pinfunction "A1_A1") (pintype "passive"))
      (node (ref "K1") (pin "COM") (pinfunction "COM_COM") (pintype "passive"))
      (node (ref "L1") (pin "2") (pinfunction "2_2") (pintype "passive"))
      (node (ref "OC1") (pin "4") (pinfunction "CT_4") (pintype "passive"))
      (node (ref "OC2") (pin "4") (pinfunction "CT_4") (pintype "passive"))
      (node (ref "R27") (pin "2") (pinfunction "2_2") (pintype "passive"))
      (node (ref "R6") (pin "3") (pinfunction "CW_3") (pintype "passive"))
      (node (ref "U1") (pin "6") (pinfunction "FB_6") (pintype "bidirectional"))
      (node (ref "U3") (pin "4") (pinfunction "FB_4") (pintype "input"))
    )
    (net (code "5") (name "/5V_RPI") (class "Default")
      (node (ref "A1") (pin "2") (pinfunction "5V[1]_2") (pintype "power_in"))
      (node (ref "A1") (pin "4") (pinfunction "5V[2]_4") (pintype "power_in"))
      (node (ref "C11") (pin "2") (pinfunction "A_2") (pintype "passive"))
      (node (ref "C17") (pin "2") (pinfunction "2_2") (pintype "passive"))
      (node (ref "C19") (pin "1") (pinfunction "1_1") (pintype "passive"))
      (node (ref "C22") (pin "2") (pinfunction "A_2") (pintype "passive"))
      (node (ref "K1") (pin "NC") (pinfunction "NC_NC") (pintype "passive"))
    )
    (net (code "6") (name "/7.4v") (class "Default")
      (node (ref "B1") (pin "B2+") (pinfunction "B2+_B2+") (pintype "passive"))
      (node (ref "B1") (pin "B3-") (pinfunction "B3-_B3-") (pintype "passive"))
      (node (ref "M1") (pin "B2") (pinfunction "B2_B2") (pintype "passive"))
    )
    (net (code "7") (name "/11.1v") (class "Default")
      (node (ref "B1") (pin "B3+") (pinfunction "B3+_B3+") (pintype "passive"))
      (node (ref "M1") (pin "B+") (pinfunction "B+_B+") (pintype "passive"))
      (node (ref "R35") (pin "2") (pinfunction "2_2") (pintype "passive"))
    )
    (net (code "8") (name "/12V_IN_D2") (class "Default")
      (node (ref "ARD1") (pin "30") (pinfunction "VIN_30") (pintype "power_in"))
      (node (ref "C1") (pin "2") (pinfunction "2_2") (pintype "passive"))
      (node (ref "C13") (pin "2") (pinfunction "2_2") (pintype "passive"))
      (node (ref "C16") (pin "2") (pinfunction "A_2") (pintype "passive"))
      (node (ref "C2") (pin "P") (pinfunction "P_P") (pintype "passive"))
      (node (ref "C3") (pin "P") (pinfunction "P_P") (pintype "passive"))
      (node (ref "C4") (pin "2") (pinfunction "A_2") (pintype "passive"))
      (node (ref "D2") (pin "1") (pinfunction "K_1") (pintype "passive"))
      (node (ref "P1") (pin "1") (pinfunction "1_1") (pintype "passive"))
      (node (ref "S1") (pin "1") (pinfunction "A1_1") (pintype "passive"))
      (node (ref "S1") (pin "2") (pinfunction "A2_2") (pintype "passive"))
      (node (ref "U1") (pin "2") (pinfunction "VIN_2") (pintype "input"))
      (node (ref "U3") (pin "1") (pinfunction "+VIN_1") (pintype "power_in"))
    )
    (net (code "9") (name "/12V_Lm555") (class "Default")
      (node (ref "D2") (pin "2") (pinfunction "A_2") (pintype "passive"))
      (node (ref "F1") (pin "2") (pinfunction "2_2") (pintype "passive"))
      (node (ref "R17") (pin "2") (pinfunction "2_2") (pintype "passive"))
    )
    (net (code "10") (name "/A0") (class "Default")
      (node (ref "ARD1") (pin "19") (pinfunction "A0_19") (pintype "passive"))
      (node (ref "R24") (pin "1") (pinfunction "1_1") (pintype "passive"))
    )
    (net (code "11") (name "/A1") (class "Default")
      (node (ref "ARD1") (pin "20") (pinfunction "A1_20") (pintype "passive"))
      (node (ref "R30") (pin "1") (pinfunction "1_1") (pintype "passive"))
    )
    (net (code "12") (name "/A2") (class "Default")
      (node (ref "ARD1") (pin "21") (pinfunction "A2_21") (pintype "passive"))
      (node (ref "R31") (pin "1") (pinfunction "1_1") (pintype "passive"))
    )
    (net (code "13") (name "/A3") (class "Default")
      (node (ref "ARD1") (pin "22") (pinfunction "A3_22") (pintype "passive"))
      (node (ref "R32") (pin "1") (pinfunction "1_1") (pintype "passive"))
    )
    (net (code "14") (name "/A4") (class "Default")
      (node (ref "ARD1") (pin "23") (pinfunction "A4_23") (pintype "passive"))
      (node (ref "R33") (pin "1") (pinfunction "1_1") (pintype "passive"))
    )
    (net (code "15") (name "/A5") (class "Default")
      (node (ref "ARD1") (pin "24") (pinfunction "A5_24") (pintype "passive"))
      (node (ref "D13") (pin "1") (pinfunction "C_1") (pintype "passive"))
      (node (ref "P1") (pin "2") (pinfunction "2_2") (pintype "passive"))
      (node (ref "R1") (pin "2") (pinfunction "2_2") (pintype "passive"))
      (node (ref "R25") (pin "1") (pinfunction "1_1") (pintype "passive"))
    )
    (net (code "16") (name "/A6") (class "Default")
      (node (ref "ARD1") (pin "25") (pinfunction "A6_25") (pintype "passive"))
      (node (ref "C15") (pin "2") (pinfunction "2_2") (pintype "passive"))
      (node (ref "C18") (pin "2") (pinfunction "A_2") (pintype "passive"))
      (node (ref "R35") (pin "1") (pinfunction "1_1") (pintype "passive"))
      (node (ref "R43") (pin "2") (pinfunction "2_2") (pintype "passive"))
    )
    (net (code "17") (name "/A7") (class "Default")
      (node (ref "ARD1") (pin "26") (pinfunction "A7_26") (pintype "passive"))
      (node (ref "R6") (pin "2") (pinfunction "WIPER_2") (pintype "passive"))
    )
    (net (code "18") (name "/Adc1") (class "Default")
      (node (ref "L2") (pin "1") (pinfunction "1_1") (pintype "passive"))
      (node (ref "P2") (pin "1") (pinfunction "1_1") (pintype "passive"))
      (node (ref "T1") (pin "7") (pinfunction "7_7") (pintype "bidirectional"))
    )
    (net (code "19") (name "/Adc2") (class "Default")
      (node (ref "D4") (pin "4") (pinfunction "2_~_4") (pintype "passive"))
      (node (ref "P2") (pin "2") (pinfunction "2_2") (pintype "passive"))
      (node (ref "R5") (pin "2") (pinfunction "WIPER_2") (pintype "passive"))
      (node (ref "T1") (pin "8") (pinfunction "8_8") (pintype "bidirectional"))
    )
    (net (code "20") (name "/Ar_5V") (class "Default")
      (node (ref "ARD1") (pin "27") (pinfunction "5V_27") (pintype "power_in"))
      (node (ref "R12") (pin "1") (pinfunction "1_1") (pintype "passive"))
    )
    (net (code "21") (name "/D2") (class "Default")
      (node (ref "ARD1") (pin "5") (pinfunction "D2_5") (pintype "passive"))
      (node (ref "C8") (pin "2") (pinfunction "2_2") (pintype "passive"))
      (node (ref "D9") (pin "C") (pinfunction "K_C") (pintype "passive"))
      (node (ref "R15") (pin "1") (pinfunction "1_1") (pintype "passive"))
      (node (ref "R7") (pin "2") (pinfunction "WIPER_2") (pintype "passive"))
    )
    (net (code "22") (name "/D3") (class "Default")
      (node (ref "ARD1") (pin "6") (pinfunction "D3_6") (pintype "passive"))
      (node (ref "C9") (pin "2") (pinfunction "2_2") (pintype "passive"))
      (node (ref "D10") (pin "C") (pinfunction "K_C") (pintype "passive"))
      (node (ref "R11") (pin "2") (pinfunction "2_2") (pintype "passive"))
      (node (ref "R8") (pin "2") (pinfunction "WIPER_2") (pintype "passive"))
    )
    (net (code "23") (name "/D4_AR") (class "Default")
      (node (ref "ARD1") (pin "7") (pinfunction "D4_7") (pintype "passive"))
      (node (ref "R36") (pin "2") (pinfunction "2_2") (pintype "passive"))
    )
    (net (code "24") (name "/D4_RASp") (class "Default")
      (node (ref "A1") (pin "7") (pinfunction "GPIO4/GPCKL0_7") (pintype "bidirectional"))
      (node (ref "R36") (pin "1") (pinfunction "1_1") (pintype "passive"))
    )
    (net (code "25") (name "/D5_AR") (class "Default")
      (node (ref "ARD1") (pin "8") (pinfunction "D5_8") (pintype "passive"))
      (node (ref "R37") (pin "2") (pinfunction "2_2") (pintype "passive"))
    )
    (net (code "26") (name "/D5_RASp") (class "Default")
      (node (ref "A1") (pin "16") (pinfunction "GEN4/GPIO23_16") (pintype "bidirectional"))
      (node (ref "R37") (pin "1") (pinfunction "1_1") (pintype "passive"))
    )
    (net (code "27") (name "/D6_AR") (class "Default")
      (node (ref "ARD1") (pin "9") (pinfunction "D6_9") (pintype "passive"))
      (node (ref "R39") (pin "2") (pinfunction "2_2") (pintype "passive"))
    )
    (net (code "28") (name "/D6_RASp") (class "Default")
      (node (ref "A1") (pin "18") (pinfunction "GEN5/GPIO24_18") (pintype "bidirectional"))
      (node (ref "R39") (pin "1") (pinfunction "1_1") (pintype "passive"))
    )
    (net (code "29") (name "/D7_AR") (class "Default")
      (node (ref "ARD1") (pin "10") (pinfunction "D7_10") (pintype "passive"))
      (node (ref "R40") (pin "2") (pinfunction "2_2") (pintype "passive"))
    )
    (net (code "30") (name "/D7_RASp") (class "Default")
      (node (ref "A1") (pin "19") (pinfunction "GPIO10/MOSI_19") (pintype "bidirectional"))
      (node (ref "R40") (pin "1") (pinfunction "1_1") (pintype "passive"))
    )
    (net (code "31") (name "/D8_AR") (class "Default")
      (node (ref "ARD1") (pin "11") (pinfunction "D8_11") (pintype "passive"))
      (node (ref "R41") (pin "2") (pinfunction "2_2") (pintype "passive"))
    )
    (net (code "32") (name "/D8_RASp") (class "Default")
      (node (ref "A1") (pin "21") (pinfunction "GPIO9/MISO_21") (pintype "bidirectional"))
      (node (ref "R41") (pin "1") (pinfunction "1_1") (pintype "passive"))
    )
    (net (code "33") (name "/D9_AR") (class "Default")
      (node (ref "ARD1") (pin "12") (pinfunction "D9_12") (pintype "passive"))
      (node (ref "R42") (pin "2") (pinfunction "2_2") (pintype "passive"))
    )
    (net (code "34") (name "/D9_RASp") (class "Default")
      (node (ref "A1") (pin "23") (pinfunction "GPIO11/SCLK_23") (pintype "bidirectional"))
      (node (ref "R42") (pin "1") (pinfunction "1_1") (pintype "passive"))
    )
    (net (code "35") (name "/D10") (class "Default")
      (node (ref "ARD1") (pin "13") (pinfunction "D10_13") (pintype "passive"))
      (node (ref "R14") (pin "2") (pinfunction "2_2") (pintype "passive"))
    )
    (net (code "36") (name "/D11") (class "Default")
      (node (ref "ARD1") (pin "14") (pinfunction "D11_14") (pintype "passive"))
      (node (ref "R34") (pin "1") (pinfunction "1_1") (pintype "passive"))
    )
    (net (code "37") (name "/D12") (class "Default")
      (node (ref "ARD1") (pin "16") (pinfunction "D13_16") (pintype "passive"))
      (node (ref "R13") (pin "2") (pinfunction "2_2") (pintype "passive"))
    )
    (net (code "38") (name "/D13") (class "Default")
      (node (ref "ARD1") (pin "15") (pinfunction "D12_15") (pintype "passive"))
      (node (ref "R19") (pin "1") (pinfunction "1_1") (pintype "passive"))
      (node (ref "R44") (pin "2") (pinfunction "2_2") (pintype "passive"))
    )
    (net (code "39") (name "/LM555_3") (class "Default")
      (node (ref "LS1") (pin "1") (pinfunction "1_1") (pintype "passive"))
      (node (ref "U2") (pin "3") (pinfunction "OUT_3") (pintype "output"))
    )
    (net (code "40") (name "/LM555_4") (class "Default")
      (node (ref "Q3") (pin "3") (pinfunction "C_3") (pintype "passive"))
      (node (ref "R10") (pin "2") (pinfunction "2_2") (pintype "passive"))
      (node (ref "U2") (pin "4") (pinfunction "~{RESET}_4") (pintype "input"))
    )
    (net (code "41") (name "/LM555_5") (class "Default")
      (node (ref "C21") (pin "1") (pinfunction "1_1") (pintype "passive"))
      (node (ref "U2") (pin "5") (pinfunction "CONT_5") (pintype "input"))
    )
    (net (code "42") (name "/LM555_6_2") (class "Default")
      (node (ref "C20") (pin "1") (pinfunction "P_1") (pintype "passive"))
      (node (ref "R23") (pin "2") (pinfunction "2_2") (pintype "passive"))
      (node (ref "U2") (pin "2") (pinfunction "TRIG_2") (pintype "input"))
      (node (ref "U2") (pin "6") (pinfunction "THRES_6") (pintype "input"))
    )
    (net (code "43") (name "/LM555_7") (class "Default")
      (node (ref "R21") (pin "2") (pinfunction "2_2") (pintype "passive"))
      (node (ref "R23") (pin "1") (pinfunction "1_1") (pintype "passive"))
      (node (ref "U2") (pin "7") (pinfunction "DISCH_7") (pintype "open_collector"))
    )
    (net (code "44") (name "/LM2596_OUT") (class "Default")
      (node (ref "C5") (pin "1") (pinfunction "1_1") (pintype "passive"))
      (node (ref "D3") (pin "2") (pinfunction "K_2") (pintype "passive"))
      (node (ref "L1") (pin "1") (pinfunction "1_1") (pintype "passive"))
      (node (ref "U1") (pin "1") (pinfunction "SW_1") (pintype "output"))
      (node (ref "U3") (pin "2") (pinfunction "OUT_2") (pintype "power_in"))
    )
    (net (code "45") (name "/RASp_A0") (class "Default")
      (node (ref "A1") (pin "29") (pinfunction "GPIO5_29") (pintype "bidirectional"))
      (node (ref "R24") (pin "2") (pinfunction "2_2") (pintype "passive"))
    )
    (net (code "46") (name "/RASp_A1") (class "Default")
      (node (ref "A1") (pin "31") (pinfunction "GPIO6_31") (pintype "bidirectional"))
      (node (ref "R30") (pin "2") (pinfunction "2_2") (pintype "passive"))
    )
    (net (code "47") (name "/RASp_A2") (class "Default")
      (node (ref "A1") (pin "33") (pinfunction "GPIO13_33") (pintype "bidirectional"))
      (node (ref "R31") (pin "2") (pinfunction "2_2") (pintype "passive"))
    )
    (net (code "48") (name "/RASp_A3") (class "Default")
      (node (ref "A1") (pin "35") (pinfunction "GPIO19_35") (pintype "bidirectional"))
      (node (ref "R32") (pin "2") (pinfunction "2_2") (pintype "passive"))
    )
    (net (code "49") (name "/RASp_A4") (class "Default")
      (node (ref "A1") (pin "37") (pinfunction "GPIO26_37") (pintype "bidirectional"))
      (node (ref "R33") (pin "2") (pinfunction "2_2") (pintype "passive"))
    )
    (net (code "50") (name "/RASp_D11") (class "Default")
      (node (ref "A1") (pin "24") (pinfunction "~{CE0}/GPIO8_24") (pintype "bidirectional"))
      (node (ref "R34") (pin "2") (pinfunction "2_2") (pintype "passive"))
    )
    (net (code "51") (name "/Rx_HV") (class "Default")
      (node (ref "ARD1") (pin "2") (pinfunction "RX0_2") (pintype "passive"))
      (node (ref "S1") (pin "4") (pinfunction "A4_4") (pintype "passive"))
    )
    (net (code "52") (name "/Rx_LV") (class "Default")
      (node (ref "A1") (pin "10") (pinfunction "RXD0/GPIO15_10") (pintype "bidirectional"))
      (node (ref "S1") (pin "5") (pinfunction "A5_5") (pintype "passive"))
    )
    (net (code "53") (name "/SCL") (class "Default")
      (node (ref "A1") (pin "5") (pinfunction "GPIO3/SCL_5") (pintype "bidirectional"))
      (node (ref "P3") (pin "2") (pinfunction "2_2") (pintype "passive"))
    )
    (net (code "54") (name "/SDA") (class "Default")
      (node (ref "A1") (pin "3") (pinfunction "GPIO2/SDA_3") (pintype "bidirectional"))
      (node (ref "P3") (pin "1") (pinfunction "1_1") (pintype "passive"))
    )
    (net (code "55") (name "/SW7") (class "Default")
      (node (ref "R28") (pin "2") (pinfunction "2_2") (pintype "passive"))
      (node (ref "S1") (pin "7") (pinfunction "B6_7") (pintype "passive"))
    )
    (net (code "56") (name "/SW8") (class "Default")
      (node (ref "R28") (pin "1") (pinfunction "1_1") (pintype "passive"))
      (node (ref "R29") (pin "2") (pinfunction "2_2") (pintype "passive"))
      (node (ref "S1") (pin "8") (pinfunction "B5_8") (pintype "passive"))
    )
    (net (code "57") (name "/SW9") (class "Default")
      (node (ref "Q2") (pin "3") (pinfunction "D_3") (pintype "passive"))
      (node (ref "R27") (pin "1") (pinfunction "1_1") (pintype "passive"))
      (node (ref "S1") (pin "9") (pinfunction "B4_9") (pintype "passive"))
    )
    (net (code "58") (name "/SW10") (class "Default")
      (node (ref "Q2") (pin "2") (pinfunction "S_2") (pintype "passive"))
      (node (ref "R26") (pin "1") (pinfunction "1_1") (pintype "passive"))
      (node (ref "S1") (pin "10") (pinfunction "B3_10") (pintype "passive"))
    )
    (net (code "59") (name "/SW11") (class "Default")
      (node (ref "C10") (pin "2") (pinfunction "2_2") (pintype "passive"))
      (node (ref "C12") (pin "P") (pinfunction "P_P") (pintype "passive"))
      (node (ref "C14") (pin "2") (pinfunction "A_2") (pintype "passive"))
      (node (ref "M1") (pin "P+") (pinfunction "P+_P+") (pintype "passive"))
      (node (ref "S1") (pin "11") (pinfunction "B2_11") (pintype "passive"))
    )
    (net (code "60") (name "/SW12") (class "Default")
      (node (ref "R10") (pin "1") (pinfunction "1_1") (pintype "passive"))
      (node (ref "R21") (pin "1") (pinfunction "1_1") (pintype "passive"))
      (node (ref "S1") (pin "12") (pinfunction "B1_12") (pintype "passive"))
      (node (ref "U2") (pin "8") (pinfunction "VCC_8") (pintype "power_in"))
    )
    (net (code "61") (name "/Sa1") (class "Default")
      (node (ref "D7") (pin "2") (pinfunction "AC1_2") (pintype "passive"))
      (node (ref "T1") (pin "3") (pinfunction "3_3") (pintype "bidirectional"))
    )
    (net (code "62") (name "/Sa2") (class "Default")
      (node (ref "D7") (pin "4") (pinfunction "AC2_4") (pintype "passive"))
      (node (ref "T1") (pin "4") (pinfunction "4_4") (pintype "bidirectional"))
    )
    (net (code "63") (name "/Sb1") (class "Default")
      (node (ref "D8") (pin "2") (pinfunction "AC1_2") (pintype "passive"))
      (node (ref "T1") (pin "5") (pinfunction "5_5") (pintype "bidirectional"))
    )
    (net (code "64") (name "/Sb2") (class "Default")
      (node (ref "D8") (pin "4") (pinfunction "AC2_4") (pintype "passive"))
      (node (ref "T1") (pin "6") (pinfunction "6_6") (pintype "bidirectional"))
    )
    (net (code "65") (name "/Tx_HV") (class "Default")
      (node (ref "ARD1") (pin "1") (pinfunction "TX1_1") (pintype "passive"))
      (node (ref "S1") (pin "6") (pinfunction "A6_6") (pintype "passive"))
    )
    (net (code "66") (name "/Tx_LV") (class "Default")
      (node (ref "A1") (pin "8") (pinfunction "TXD0/GPIO14_8") (pintype "bidirectional"))
      (node (ref "S1") (pin "3") (pinfunction "A3_3") (pintype "passive"))
    )
    (net (code "67") (name "GND") (class "Default")
      (node (ref "A1") (pin "14") (pinfunction "GND[4]_14") (pintype "power_in"))
      (node (ref "A1") (pin "20") (pinfunction "GND[5]_20") (pintype "power_in"))
      (node (ref "A1") (pin "25") (pinfunction "GND[2]_25") (pintype "power_in"))
      (node (ref "A1") (pin "30") (pinfunction "GND[6]_30") (pintype "power_in"))
      (node (ref "A1") (pin "34") (pinfunction "GND[7]_34") (pintype "power_in"))
      (node (ref "A1") (pin "39") (pinfunction "GND[3]_39") (pintype "power_in"))
      (node (ref "A1") (pin "6") (pinfunction "GND[8]_6") (pintype "power_in"))
      (node (ref "A1") (pin "9") (pinfunction "GND[1]_9") (pintype "power_in"))
      (node (ref "ARD1") (pin "29") (pinfunction "GND_29") (pintype "power_in"))
      (node (ref "ARD1") (pin "4") (pinfunction "GND_4") (pintype "power_in"))
      (node (ref "B1") (pin "B1-") (pinfunction "B1-_B1-") (pintype "passive"))
      (node (ref "C1") (pin "1") (pinfunction "1_1") (pintype "passive"))
      (node (ref "C10") (pin "1") (pinfunction "1_1") (pintype "passive"))
      (node (ref "C11") (pin "1") (pinfunction "C_1") (pintype "passive"))
      (node (ref "C12") (pin "N") (pinfunction "N_N") (pintype "passive"))
      (node (ref "C13") (pin "1") (pinfunction "1_1") (pintype "passive"))
      (node (ref "C14") (pin "1") (pinfunction "C_1") (pintype "passive"))
      (node (ref "C15") (pin "1") (pinfunction "1_1") (pintype "passive"))
      (node (ref "C16") (pin "1") (pinfunction "C_1") (pintype "passive"))
      (node (ref "C17") (pin "1") (pinfunction "1_1") (pintype "passive"))
      (node (ref "C18") (pin "1") (pinfunction "C_1") (pintype "passive"))
      (node (ref "C19") (pin "2") (pinfunction "2_2") (pintype "passive"))
      (node (ref "C2") (pin "N") (pinfunction "N_N") (pintype "passive"))
      (node (ref "C20") (pin "2") (pinfunction "N_2") (pintype "passive"))
      (node (ref "C21") (pin "2") (pinfunction "2_2") (pintype "passive"))
      (node (ref "C22") (pin "1") (pinfunction "C_1") (pintype "passive"))
      (node (ref "C3") (pin "N") (pinfunction "N_N") (pintype "passive"))
      (node (ref "C4") (pin "1") (pinfunction "C_1") (pintype "passive"))
      (node (ref "C6") (pin "N") (pinfunction "N_N") (pintype "passive"))
      (node (ref "C7") (pin "N") (pinfunction "N_N") (pintype "passive"))
      (node (ref "C8") (pin "1") (pinfunction "1_1") (pintype "passive"))
      (node (ref "C9") (pin "1") (pinfunction "1_1") (pintype "passive"))
      (node (ref "D13") (pin "2") (pinfunction "A_2") (pintype "passive"))
      (node (ref "D3") (pin "1") (pinfunction "A_1") (pintype "passive"))
      (node (ref "LS1") (pin "2") (pinfunction "2_2") (pintype "passive"))
      (node (ref "M1") (pin "B-") (pinfunction "B-_B-") (pintype "passive"))
      (node (ref "M1") (pin "P-") (pinfunction "P-_P-") (pintype "passive"))
      (node (ref "P1") (pin "3") (pinfunction "3_3") (pintype "passive"))
      (node (ref "P3") (pin "3") (pinfunction "3_3") (pintype "passive"))
      (node (ref "Q1") (pin "1") (pinfunction "E_1") (pintype "passive"))
      (node (ref "Q3") (pin "2") (pinfunction "E_2") (pintype "passive"))
      (node (ref "R16") (pin "1") (pinfunction "1_1") (pintype "passive"))
      (node (ref "R18") (pin "1") (pinfunction "1_1") (pintype "passive"))
      (node (ref "R20") (pin "2") (pinfunction "2_2") (pintype "passive"))
      (node (ref "R25") (pin "2") (pinfunction "2_2") (pintype "passive"))
      (node (ref "R29") (pin "1") (pinfunction "1_1") (pintype "passive"))
      (node (ref "R43") (pin "1") (pinfunction "1_1") (pintype "passive"))
      (node (ref "R44") (pin "1") (pinfunction "1_1") (pintype "passive"))
      (node (ref "R6") (pin "1") (pinfunction "CCW_1") (pintype "passive"))
      (node (ref "R7") (pin "1") (pinfunction "CCW_1") (pintype "passive"))
      (node (ref "R8") (pin "1") (pinfunction "CCW_1") (pintype "passive"))
      (node (ref "R9") (pin "1") (pinfunction "1_1") (pintype "passive"))
      (node (ref "T1") (pin "1") (pinfunction "1_1") (pintype "bidirectional"))
      (node (ref "U1") (pin "4") (pinfunction "GND_4") (pintype "power_in"))
      (node (ref "U1") (pin "8") (pinfunction "GND_8") (pintype "power_in"))
      (node (ref "U2") (pin "1") (pinfunction "GND_1") (pintype "power_in"))
      (node (ref "U3") (pin "3") (pinfunction "GND_3") (pintype "power_in"))
      (node (ref "U3") (pin "5") (pinfunction "~{ON}/OFF_5") (pintype "input"))
      (node (ref "U3") (pin "6") (pinfunction "GND_6") (pintype "power_in"))
      (node (ref "count_a_ok") (pin "2") (pinfunction "K_2") (pintype "passive"))
      (node (ref "count_b_ng") (pin "2") (pinfunction "K_2") (pintype "passive"))
      (node (ref "link") (pin "2") (pinfunction "K_2") (pintype "passive"))
      (node (ref "power") (pin "2") (pinfunction "K_2") (pintype "passive"))
      (node (ref "warning") (pin "2") (pinfunction "K_2") (pintype "passive"))
    )
    (net (code "68") (name "Net-(D4-+)") (class "Default")
      (node (ref "D4") (pin "1") (pinfunction "+_1") (pintype "passive"))
      (node (ref "R1") (pin "1") (pinfunction "1_1") (pintype "passive"))
    )
    (net (code "69") (name "Net-(D4--)") (class "Default")
      (node (ref "D4") (pin "3") (pinfunction "-_3") (pintype "passive"))
      (node (ref "R20") (pin "1") (pinfunction "1_1") (pintype "passive"))
    )
    (net (code "70") (name "Net-(D4-1_~)") (class "Default")
      (node (ref "D4") (pin "2") (pinfunction "1_~_2") (pintype "passive"))
      (node (ref "L2") (pin "2") (pinfunction "2_2") (pintype "passive"))
      (node (ref "R38") (pin "1") (pinfunction "1_1") (pintype "passive"))
    )
    (net (code "71") (name "Net-(D5-K)") (class "Default")
      (node (ref "D5") (pin "C") (pinfunction "K_C") (pintype "passive"))
      (node (ref "OC1") (pin "1") (pinfunction "A_1") (pintype "passive"))
      (node (ref "R22") (pin "2") (pinfunction "2_2") (pintype "passive"))
    )
    (net (code "72") (name "Net-(D6-K)") (class "Default")
      (node (ref "D6") (pin "C") (pinfunction "K_C") (pintype "passive"))
      (node (ref "OC2") (pin "1") (pinfunction "A_1") (pintype "passive"))
      (node (ref "R3") (pin "2") (pinfunction "2_2") (pintype "passive"))
    )
    (net (code "73") (name "Net-(D7-NEG)") (class "Default")
      (node (ref "D7") (pin "3") (pinfunction "NEG_3") (pintype "passive"))
      (node (ref "R2") (pin "1") (pinfunction "1_1") (pintype "passive"))
    )
    (net (code "74") (name "Net-(D7-POS)") (class "Default")
      (node (ref "D7") (pin "1") (pinfunction "POS_1") (pintype "passive"))
      (node (ref "R22") (pin "1") (pinfunction "1_1") (pintype "passive"))
    )
    (net (code "75") (name "Net-(D8-NEG)") (class "Default")
      (node (ref "D8") (pin "3") (pinfunction "NEG_3") (pintype "passive"))
      (node (ref "R4") (pin "1") (pinfunction "1_1") (pintype "passive"))
    )
    (net (code "76") (name "Net-(D8-POS)") (class "Default")
      (node (ref "D8") (pin "1") (pinfunction "POS_1") (pintype "passive"))
      (node (ref "R3") (pin "1") (pinfunction "1_1") (pintype "passive"))
    )
    (net (code "77") (name "Net-(D9-PadA)") (class "Default")
      (node (ref "D9") (pin "A") (pinfunction "A_A") (pintype "passive"))
      (node (ref "R9") (pin "2") (pinfunction "2_2") (pintype "passive"))
    )
    (net (code "78") (name "Net-(D10-PadA)") (class "Default")
      (node (ref "D10") (pin "A") (pinfunction "A_A") (pintype "passive"))
      (node (ref "R16") (pin "2") (pinfunction "2_2") (pintype "passive"))
    )
    (net (code "79") (name "Net-(F1-Pad1)") (class "Default")
      (node (ref "F1") (pin "1") (pinfunction "1_1") (pintype "passive"))
      (node (ref "T1") (pin "2") (pinfunction "2_2") (pintype "bidirectional"))
    )
    (net (code "80") (name "Net-(OC1-C)") (class "Default")
      (node (ref "D5") (pin "A") (pinfunction "A_A") (pintype "passive"))
      (node (ref "OC1") (pin "2") (pinfunction "C_2") (pintype "passive"))
      (node (ref "R2") (pin "2") (pinfunction "2_2") (pintype "passive"))
    )
    (net (code "81") (name "Net-(OC1-ET)") (class "Default")
      (node (ref "OC1") (pin "3") (pinfunction "ET_3") (pintype "passive"))
      (node (ref "R7") (pin "3") (pinfunction "CW_3") (pintype "passive"))
    )
    (net (code "82") (name "Net-(OC2-C)") (class "Default")
      (node (ref "D6") (pin "A") (pinfunction "A_A") (pintype "passive"))
      (node (ref "OC2") (pin "2") (pinfunction "C_2") (pintype "passive"))
      (node (ref "R4") (pin "2") (pinfunction "2_2") (pintype "passive"))
    )
    (net (code "83") (name "Net-(OC2-ET)") (class "Default")
      (node (ref "OC2") (pin "3") (pinfunction "ET_3") (pintype "passive"))
      (node (ref "R8") (pin "3") (pinfunction "CW_3") (pintype "passive"))
    )
    (net (code "84") (name "Net-(Q1-B)") (class "Default")
      (node (ref "Q1") (pin "3") (pinfunction "B_3") (pintype "passive"))
      (node (ref "R19") (pin "2") (pinfunction "2_2") (pintype "passive"))
    )
    (net (code "85") (name "Net-(Q1-C)") (class "Default")
      (node (ref "D11") (pin "A") (pinfunction "A_A") (pintype "passive"))
      (node (ref "K1") (pin "A2") (pinfunction "A2_A2") (pintype "passive"))
      (node (ref "Q1") (pin "2") (pinfunction "C_2") (pintype "passive"))
    )
    (net (code "86") (name "Net-(Q3-B)") (class "Default")
      (node (ref "Q3") (pin "1") (pinfunction "B_1") (pintype "passive"))
      (node (ref "R17") (pin "1") (pinfunction "1_1") (pintype "passive"))
      (node (ref "R18") (pin "2") (pinfunction "2_2") (pintype "passive"))
    )
    (net (code "87") (name "Net-(R5-CCW)") (class "Default")
      (node (ref "R38") (pin "2") (pinfunction "2_2") (pintype "passive"))
      (node (ref "R5") (pin "1") (pinfunction "CCW_1") (pintype "passive"))
    )
    (net (code "88") (name "Net-(U1-BOOST)") (class "Default")
      (node (ref "C5") (pin "2") (pinfunction "2_2") (pintype "passive"))
      (node (ref "U1") (pin "3") (pinfunction "BOOST_3") (pintype "bidirectional"))
    )
    (net (code "89") (name "Net-(count_a_ok-A)") (class "Default")
      (node (ref "R15") (pin "2") (pinfunction "2_2") (pintype "passive"))
      (node (ref "count_a_ok") (pin "1") (pinfunction "A_1") (pintype "passive"))
    )
    (net (code "90") (name "Net-(count_b_ng-A)") (class "Default")
      (node (ref "R11") (pin "1") (pinfunction "1_1") (pintype "passive"))
      (node (ref "count_b_ng") (pin "1") (pinfunction "A_1") (pintype "passive"))
    )
    (net (code "91") (name "Net-(link-A)") (class "Default")
      (node (ref "R14") (pin "1") (pinfunction "1_1") (pintype "passive"))
      (node (ref "link") (pin "1") (pinfunction "A_1") (pintype "passive"))
    )
    (net (code "92") (name "Net-(power-A)") (class "Default")
      (node (ref "R12") (pin "2") (pinfunction "2_2") (pintype "passive"))
      (node (ref "power") (pin "1") (pinfunction "A_1") (pintype "passive"))
    )
    (net (code "93") (name "Net-(warning-A)") (class "Default")
      (node (ref "R13") (pin "1") (pinfunction "1_1") (pintype "passive"))
      (node (ref "warning") (pin "1") (pinfunction "A_1") (pintype "passive"))
    )
    (net (code "94") (name "unconnected-(A1-3V3[2]-Pad17)") (class "Default")
      (node (ref "A1") (pin "17") (pinfunction "3V3[2]_17") (pintype "power_in"))
    )
    (net (code "95") (name "unconnected-(A1-GEN{slash}6GPIO25-Pad22)") (class "Default")
      (node (ref "A1") (pin "22") (pinfunction "GEN/6GPIO25_22") (pintype "bidirectional"))
    )
    (net (code "96") (name "unconnected-(A1-GPIO12-Pad32)") (class "Default")
      (node (ref "A1") (pin "32") (pinfunction "GPIO12_32") (pintype "bidirectional"))
    )
    (net (code "97") (name "unconnected-(A1-GPIO16-Pad36)") (class "Default")
      (node (ref "A1") (pin "36") (pinfunction "GPIO16_36") (pintype "bidirectional"))
    )
    (net (code "98") (name "unconnected-(A1-GPIO17{slash}GEN0-Pad11)") (class "Default")
      (node (ref "A1") (pin "11") (pinfunction "GPIO17/GEN0_11") (pintype "bidirectional"))
    )
    (net (code "99") (name "unconnected-(A1-GPIO18-Pad12)") (class "Default")
      (node (ref "A1") (pin "12") (pinfunction "GPIO18_12") (pintype "bidirectional"))
    )
    (net (code "100") (name "unconnected-(A1-GPIO20-Pad38)") (class "Default")
      (node (ref "A1") (pin "38") (pinfunction "GPIO20_38") (pintype "bidirectional"))
    )
    (net (code "101") (name "unconnected-(A1-GPIO21-Pad40)") (class "Default")
      (node (ref "A1") (pin "40") (pinfunction "GPIO21_40") (pintype "bidirectional"))
    )
    (net (code "102") (name "unconnected-(A1-GPIO22{slash}GEN3-Pad15)") (class "Default")
      (node (ref "A1") (pin "15") (pinfunction "GPIO22/GEN3_15") (pintype "bidirectional"))
    )
    (net (code "103") (name "unconnected-(A1-GPIO27{slash}GEN2-Pad13)") (class "Default")
      (node (ref "A1") (pin "13") (pinfunction "GPIO27/GEN2_13") (pintype "bidirectional"))
    )
    (net (code "104") (name "unconnected-(A1-ID_SC-Pad28)") (class "Default")
      (node (ref "A1") (pin "28") (pinfunction "ID_SC_28") (pintype "bidirectional"))
    )
    (net (code "105") (name "unconnected-(A1-ID_SD-Pad27)") (class "Default")
      (node (ref "A1") (pin "27") (pinfunction "ID_SD_27") (pintype "bidirectional"))
    )
    (net (code "106") (name "unconnected-(A1-~{CE1{slash}}GPIO7-Pad26)") (class "Default")
      (node (ref "A1") (pin "26") (pinfunction "~{CE1/}GPIO7_26") (pintype "bidirectional"))
    )
    (net (code "107") (name "unconnected-(ARD1-REF-Pad18)") (class "Default")
      (node (ref "ARD1") (pin "18") (pinfunction "REF_18") (pintype "passive"))
    )
    (net (code "108") (name "unconnected-(ARD1-RST-Pad3)") (class "Default")
      (node (ref "ARD1") (pin "3") (pinfunction "RST_3") (pintype "passive"))
    )
    (net (code "109") (name "unconnected-(ARD1-RST-Pad28)") (class "Default")
      (node (ref "ARD1") (pin "28") (pinfunction "RST_28") (pintype "passive"))
    )
    (net (code "110") (name "unconnected-(K1-PadNO)") (class "Default")
      (node (ref "K1") (pin "NO") (pinfunction "NO_NO") (pintype "passive"))
    )
    (net (code "111") (name "unconnected-(R5-CW-Pad3)") (class "Default")
      (node (ref "R5") (pin "3") (pinfunction "CW_3") (pintype "passive"))
    )
    (net (code "112") (name "unconnected-(U1-N.C.-Pad5)") (class "Default")
      (node (ref "U1") (pin "5") (pinfunction "N.C._5") (pintype "bidirectional"))
    )
    (net (code "113") (name "unconnected-(U1-ON{slash}~OFF-Pad7)") (class "Default")
      (node (ref "U1") (pin "7") (pinfunction "ON/~OFF_7") (pintype "bidirectional"))
    )
  )
)
